# PROYECTO_OSCAR.net
KiCad netlist of a schematic drawn in EAGLE
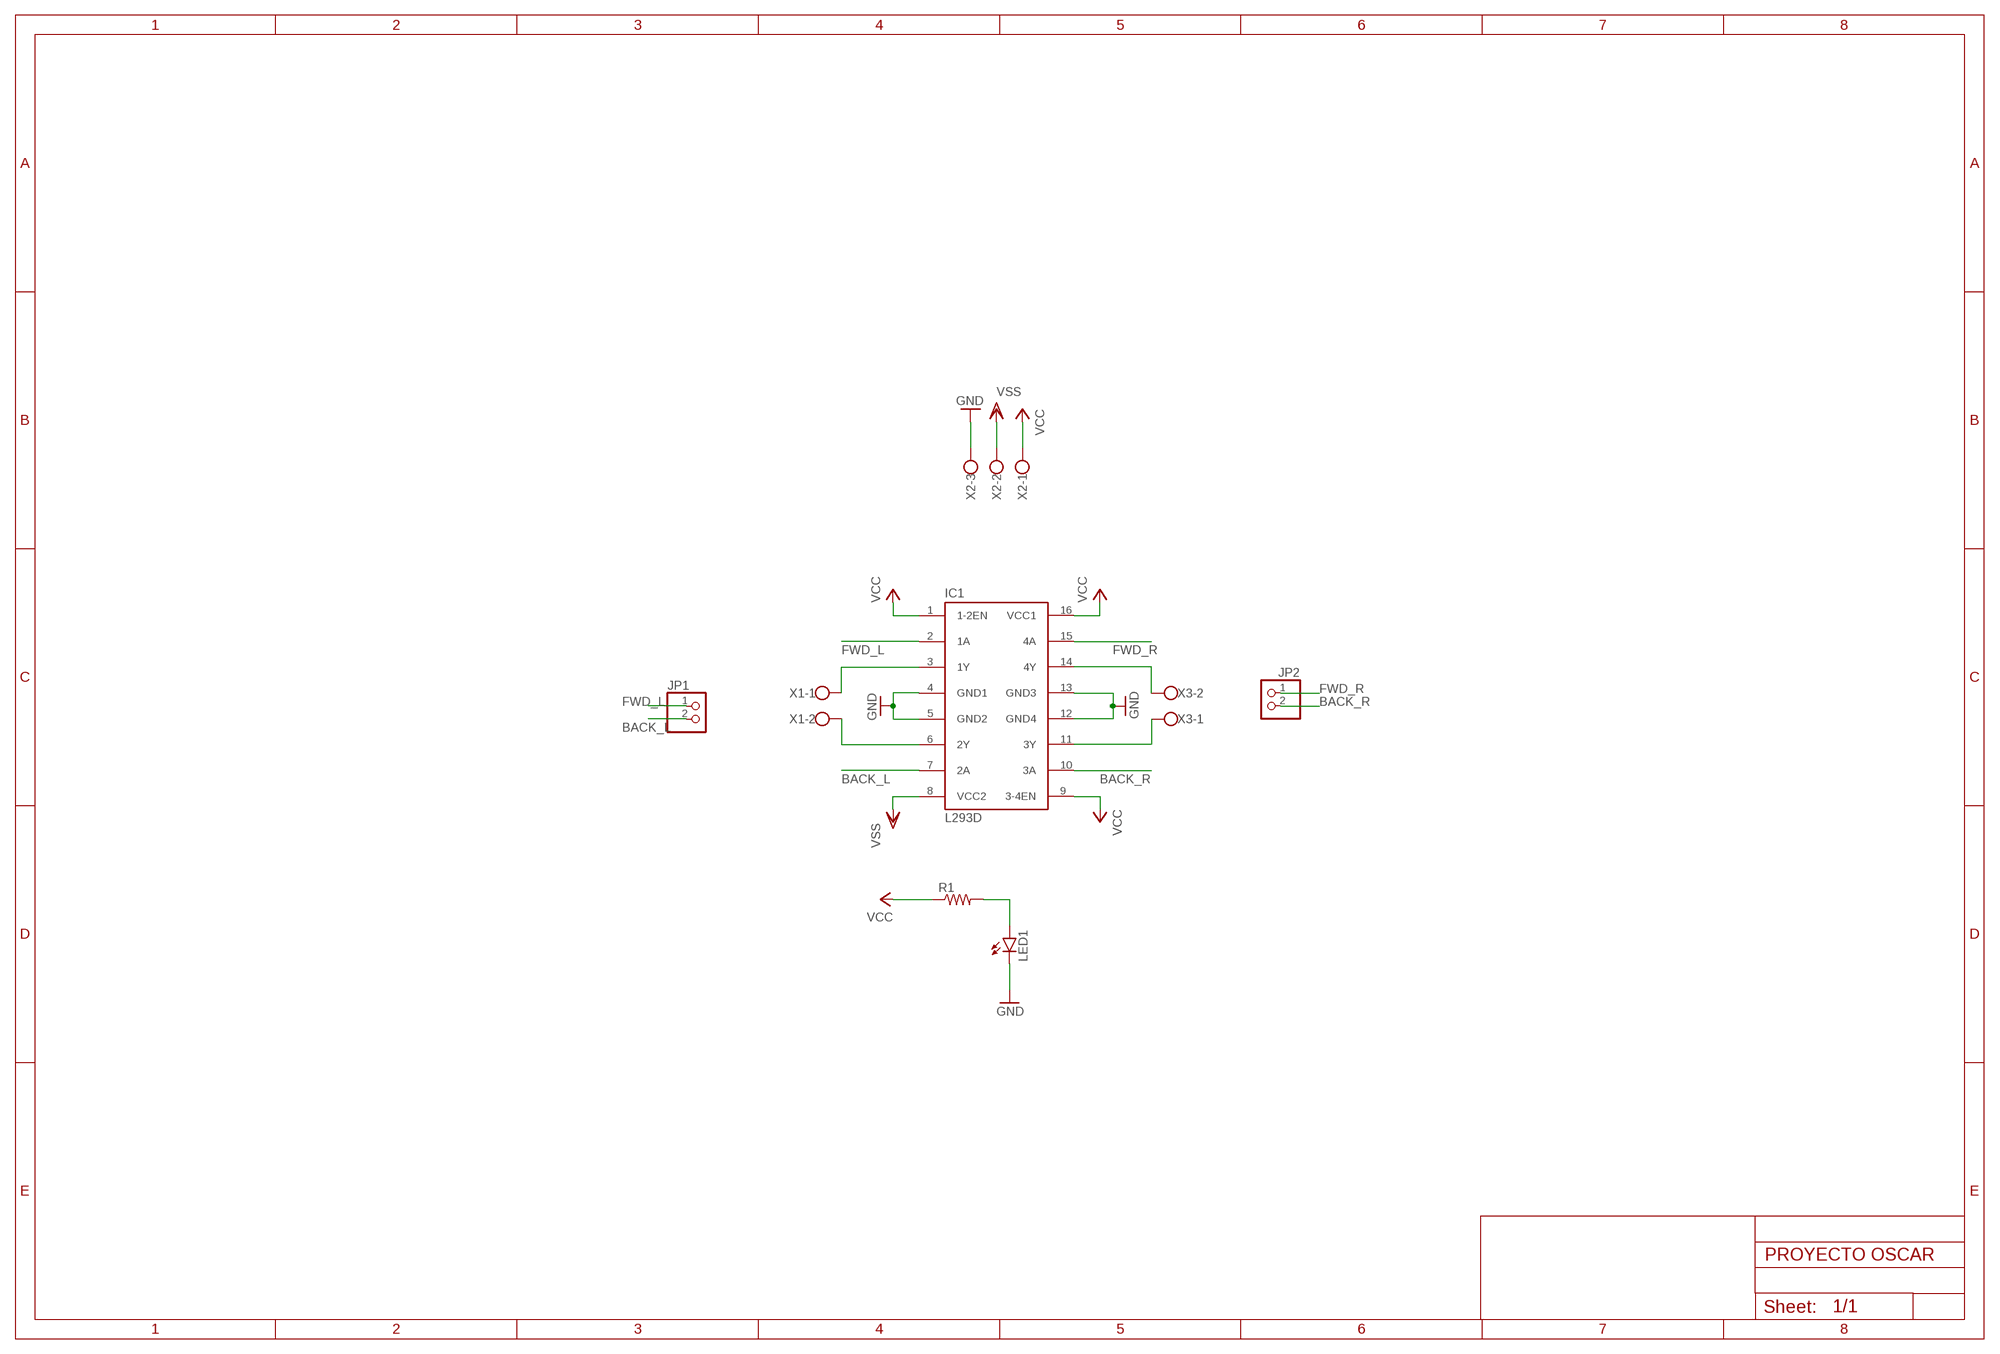
[diagram p0: schematic, sheet 1]

(export (version "E")
  (design (tool "Eeschema 10.0.6"))
  (components
    (comp (ref "IC1")
      (value "L293D")
      (footprint "eagle-import:DIL16")
      (libsource (lib "eagle-import") (part "L293D"))
    )
    (comp (ref "JP1")
      (value "PINHD-1X2")
      (footprint "eagle-import:1X02")
      (libsource (lib "eagle-import") (part "PINHD-1X2"))
    )
    (comp (ref "JP2")
      (value "PINHD-1X2")
      (footprint "eagle-import:1X02")
      (libsource (lib "eagle-import") (part "PINHD-1X2"))
    )
    (comp (ref "LED1")
      (value "LED5MM")
      (footprint "eagle-import:LED5MM")
      (libsource (lib "eagle-import") (part "LED5MM"))
    )
    (comp (ref "R1")
      (value "R-US_0204/7")
      (footprint "eagle-import:0204_7")
      (libsource (lib "eagle-import") (part "R-US_0204/7"))
    )
    (comp (ref "X1")
      (value "W237-102")
      (footprint "eagle-import:W237-102")
      (fields (field (name "MPN") "237-102"))
      (libsource (lib "eagle-import") (part "W237-102"))
    )
    (comp (ref "X2")
      (value "W237-103")
      (footprint "eagle-import:W237-103")
      (fields (field (name "MPN") "237-103"))
      (libsource (lib "eagle-import") (part "W237-103"))
    )
    (comp (ref "X3")
      (value "W237-102")
      (footprint "eagle-import:W237-102")
      (fields (field (name "MPN") "237-102"))
      (libsource (lib "eagle-import") (part "W237-102"))
    )
  )
  (nets
    (net (code "1") (name "/BACK_L") (class "Default")
      (node (ref "IC1") (pin "7") (pinfunction "2A_7") (pintype "input"))
      (node (ref "JP1") (pin "2") (pinfunction "2_2") (pintype "passive"))
    )
    (net (code "2") (name "/BACK_R") (class "Default")
      (node (ref "IC1") (pin "10") (pinfunction "3A_10") (pintype "input"))
      (node (ref "JP2") (pin "2") (pinfunction "2_2") (pintype "passive"))
    )
    (net (code "3") (name "/FWD_L") (class "Default")
      (node (ref "IC1") (pin "2") (pinfunction "1A_2") (pintype "input"))
      (node (ref "JP1") (pin "1") (pinfunction "1_1") (pintype "passive"))
    )
    (net (code "4") (name "/FWD_R") (class "Default")
      (node (ref "IC1") (pin "15") (pinfunction "4A_15") (pintype "input"))
      (node (ref "JP2") (pin "1") (pinfunction "1_1") (pintype "passive"))
    )
    (net (code "5") (name "GND") (class "Default")
      (node (ref "IC1") (pin "12") (pinfunction "GND4_12") (pintype "power_in"))
      (node (ref "IC1") (pin "13") (pinfunction "GND3_13") (pintype "power_in"))
      (node (ref "IC1") (pin "4") (pinfunction "GND1_4") (pintype "power_in"))
      (node (ref "IC1") (pin "5") (pinfunction "GND2_5") (pintype "power_in"))
      (node (ref "LED1") (pin "K") (pinfunction "C_K") (pintype "passive"))
      (node (ref "X2") (pin "3") (pinfunction "KL_3") (pintype "passive"))
    )
    (net (code "6") (name "Net-(IC1-1Y)") (class "Default")
      (node (ref "IC1") (pin "3") (pinfunction "1Y_3") (pintype "output"))
      (node (ref "X1") (pin "1") (pinfunction "KL_1") (pintype "passive"))
    )
    (net (code "7") (name "Net-(IC1-2Y)") (class "Default")
      (node (ref "IC1") (pin "6") (pinfunction "2Y_6") (pintype "output"))
      (node (ref "X1") (pin "2") (pinfunction "KL_2") (pintype "passive"))
    )
    (net (code "8") (name "Net-(IC1-3Y)") (class "Default")
      (node (ref "IC1") (pin "11") (pinfunction "3Y_11") (pintype "output"))
      (node (ref "X3") (pin "1") (pinfunction "KL_1") (pintype "passive"))
    )
    (net (code "9") (name "Net-(IC1-4Y)") (class "Default")
      (node (ref "IC1") (pin "14") (pinfunction "4Y_14") (pintype "output"))
      (node (ref "X3") (pin "2") (pinfunction "KL_2") (pintype "passive"))
    )
    (net (code "10") (name "Net-(LED1-PadA)") (class "Default")
      (node (ref "LED1") (pin "A") (pinfunction "A_A") (pintype "passive"))
      (node (ref "R1") (pin "2") (pinfunction "2_2") (pintype "passive"))
    )
    (net (code "11") (name "VCC") (class "Default")
      (node (ref "IC1") (pin "1") (pinfunction "1-2EN_1") (pintype "input"))
      (node (ref "IC1") (pin "16") (pinfunction "VCC1_16") (pintype "power_in"))
      (node (ref "IC1") (pin "9") (pinfunction "3-4EN_9") (pintype "input"))
      (node (ref "R1") (pin "1") (pinfunction "1_1") (pintype "passive"))
      (node (ref "X2") (pin "1") (pinfunction "KL_1") (pintype "passive"))
    )
    (net (code "12") (name "VSS") (class "Default")
      (node (ref "IC1") (pin "8") (pinfunction "VCC2_8") (pintype "power_in"))
      (node (ref "X2") (pin "2") (pinfunction "KL_2") (pintype "passive"))
    )
  )
)
